# Peripherial.net
KiCad netlist of a schematic drawn in Altium Designer
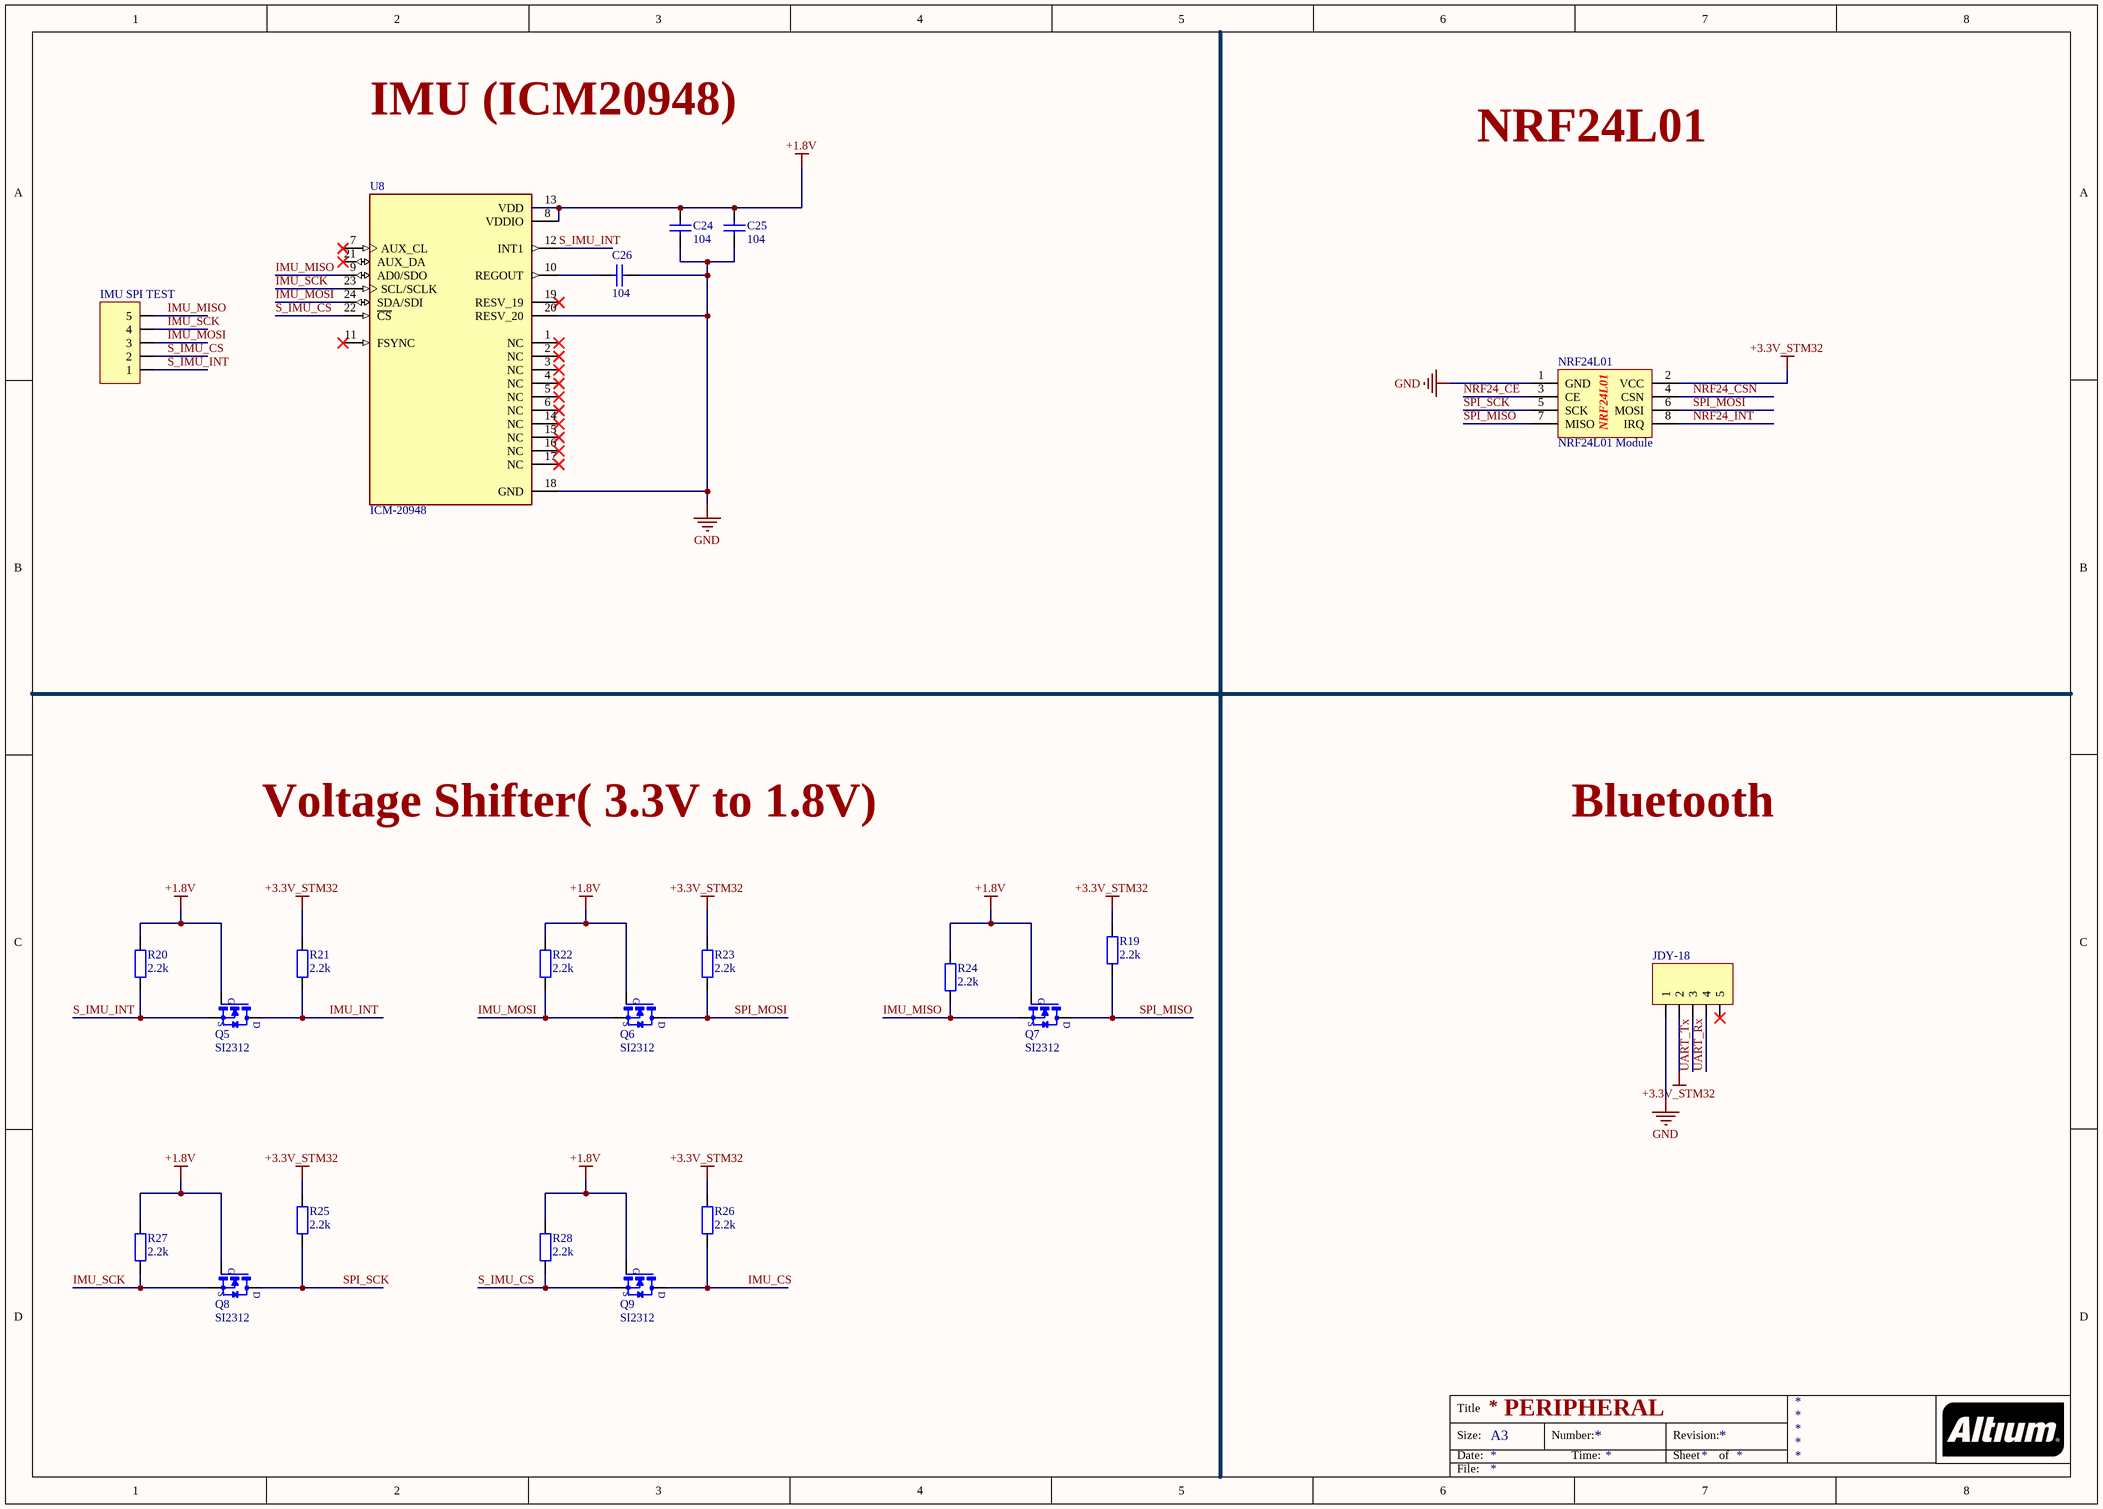
[diagram p0: Peripherial.SchDoc]

(export (version "E")
  (design (tool "Eeschema 10.0.6"))
  (components
    (comp (ref "C24")
      (value "104")
      (footprint "tu 1206")
      (description "Dán")
      (libsource (lib "Altium_Lib_by_KhueNguyenCreator") (part "Tu 1206 104 50V 20%"))
    )
    (comp (ref "C25")
      (value "104")
      (footprint "tu 1206")
      (description "Dán")
      (libsource (lib "Altium_Lib_by_KhueNguyenCreator") (part "Tu 1206 104 50V 20%"))
    )
    (comp (ref "C26")
      (value "104")
      (footprint "tu 1206")
      (description "Dán")
      (libsource (lib "Altium_Lib_by_KhueNguyenCreator") (part "Tu 1206 104 50V 20%"))
    )
    (comp (ref "IMU SPI TEST")
      (value "~")
      (footprint "JP 1x5 DT")
      (description "Cắm")
      (libsource (lib "Altium_Lib_by_KhueNguyenCreator") (part "JP 1x5 2.54 Duc Thang"))
    )
    (comp (ref "JDY-18")
      (value "JP 1x5 2.54")
      (footprint "JP 1x5 CC")
      (description "Cắm")
      (libsource (lib "Altium_Lib_by_KhueNguyenCreator") (part "JP 1x5 2.54 Cai Cong"))
    )
    (comp (ref "NRF24L01")
      (value "NRF24L01 Module")
      (footprint "NRF24L01")
      (libsource (lib "Altium_Lib_by_KhueNguyenCreator") (part "NRF24L01 Module"))
    )
    (comp (ref "Q5")
      (value "SI2312")
      (footprint "SI2312-TP:SOT23")
      (fields
        (field (name "MF") "{'manufacturer': u'Micro Commercial Components'}")
        (field (name "MP") "SI2312-TP")
      )
      (libsource (lib "*") (part "SI2312"))
    )
    (comp (ref "Q6")
      (value "SI2312")
      (footprint "SI2312-TP:SOT23")
      (fields
        (field (name "MF") "{'manufacturer': u'Micro Commercial Components'}")
        (field (name "MP") "SI2312-TP")
      )
      (libsource (lib "*") (part "SI2312"))
    )
    (comp (ref "Q7")
      (value "SI2312")
      (footprint "SI2312-TP:SOT23")
      (fields
        (field (name "MF") "{'manufacturer': u'Micro Commercial Components'}")
        (field (name "MP") "SI2312-TP")
      )
      (libsource (lib "*") (part "SI2312"))
    )
    (comp (ref "Q8")
      (value "SI2312")
      (footprint "SI2312-TP:SOT23")
      (fields
        (field (name "MF") "{'manufacturer': u'Micro Commercial Components'}")
        (field (name "MP") "SI2312-TP")
      )
      (libsource (lib "*") (part "SI2312"))
    )
    (comp (ref "Q9")
      (value "SI2312")
      (footprint "SI2312-TP:SOT23")
      (fields
        (field (name "MF") "{'manufacturer': u'Micro Commercial Components'}")
        (field (name "MP") "SI2312-TP")
      )
      (libsource (lib "*") (part "SI2312"))
    )
    (comp (ref "R19")
      (value "2.2k")
      (footprint "tro smd 0603")
      (description "Dán")
      (libsource (lib "Altium_Lib_by_KhueNguyenCreator") (part "Tro 0603 5% 2.2k"))
    )
    (comp (ref "R20")
      (value "2.2k")
      (footprint "tro smd 0603")
      (description "Dán")
      (libsource (lib "Altium_Lib_by_KhueNguyenCreator") (part "Tro 0603 5% 2.2k"))
    )
    (comp (ref "R21")
      (value "2.2k")
      (footprint "tro smd 0603")
      (description "Dán")
      (libsource (lib "Altium_Lib_by_KhueNguyenCreator") (part "Tro 0603 5% 2.2k"))
    )
    (comp (ref "R22")
      (value "2.2k")
      (footprint "tro smd 0603")
      (description "Dán")
      (libsource (lib "Altium_Lib_by_KhueNguyenCreator") (part "Tro 0603 5% 2.2k"))
    )
    (comp (ref "R23")
      (value "2.2k")
      (footprint "tro smd 0603")
      (description "Dán")
      (libsource (lib "Altium_Lib_by_KhueNguyenCreator") (part "Tro 0603 5% 2.2k"))
    )
    (comp (ref "R24")
      (value "2.2k")
      (footprint "tro smd 0603")
      (description "Dán")
      (libsource (lib "Altium_Lib_by_KhueNguyenCreator") (part "Tro 0603 5% 2.2k"))
    )
    (comp (ref "R25")
      (value "2.2k")
      (footprint "tro smd 0603")
      (description "Dán")
      (libsource (lib "Altium_Lib_by_KhueNguyenCreator") (part "Tro 0603 5% 2.2k"))
    )
    (comp (ref "R26")
      (value "2.2k")
      (footprint "tro smd 0603")
      (description "Dán")
      (libsource (lib "Altium_Lib_by_KhueNguyenCreator") (part "Tro 0603 5% 2.2k"))
    )
    (comp (ref "R27")
      (value "2.2k")
      (footprint "tro smd 0603")
      (description "Dán")
      (libsource (lib "Altium_Lib_by_KhueNguyenCreator") (part "Tro 0603 5% 2.2k"))
    )
    (comp (ref "R28")
      (value "2.2k")
      (footprint "tro smd 0603")
      (description "Dán")
      (libsource (lib "Altium_Lib_by_KhueNguyenCreator") (part "Tro 0603 5% 2.2k"))
    )
    (comp (ref "U8")
      (value "ICM-20948")
      (footprint "QFN40P300X300X105-24N")
      (description "Accelerometer, Gyroscope, Magnetometer, 9 Axis Sensor IÂ²C, SPI Output")
      (fields (field (name "MF") "{'manufacturer': u'TDK InvenSense'}"))
      (libsource (lib "SnapEDA_Library") (part "ICM-20948"))
    )
  )
  (nets
    (net (code "1") (name "+1.8V") (class "Default")
      (node (ref "C24") (pin "1") (pinfunction "1_1") (pintype "passive"))
      (node (ref "C25") (pin "1") (pinfunction "1_1") (pintype "passive"))
      (node (ref "Q5") (pin "1") (pinfunction "G_1") (pintype "passive"))
      (node (ref "Q6") (pin "1") (pinfunction "G_1") (pintype "passive"))
      (node (ref "Q7") (pin "1") (pinfunction "G_1") (pintype "passive"))
      (node (ref "Q8") (pin "1") (pinfunction "G_1") (pintype "passive"))
      (node (ref "Q9") (pin "1") (pinfunction "G_1") (pintype "passive"))
      (node (ref "R20") (pin "2") (pinfunction "2_2") (pintype "passive"))
      (node (ref "R22") (pin "2") (pinfunction "2_2") (pintype "passive"))
      (node (ref "R24") (pin "2") (pinfunction "2_2") (pintype "passive"))
      (node (ref "R27") (pin "2") (pinfunction "2_2") (pintype "passive"))
      (node (ref "R28") (pin "2") (pinfunction "2_2") (pintype "passive"))
      (node (ref "U8") (pin "13") (pinfunction "VDD_13") (pintype "power_in"))
      (node (ref "U8") (pin "8") (pinfunction "VDDIO_8") (pintype "power_in"))
    )
    (net (code "2") (name "+3.3V_STM32") (class "Default")
      (node (ref "JDY-18") (pin "2") (pinfunction "2_2") (pintype "passive"))
      (node (ref "NRF24L01") (pin "2") (pinfunction "VCC_2") (pintype "passive"))
      (node (ref "R19") (pin "2") (pinfunction "2_2") (pintype "passive"))
      (node (ref "R21") (pin "2") (pinfunction "2_2") (pintype "passive"))
      (node (ref "R23") (pin "2") (pinfunction "2_2") (pintype "passive"))
      (node (ref "R25") (pin "2") (pinfunction "2_2") (pintype "passive"))
      (node (ref "R26") (pin "2") (pinfunction "2_2") (pintype "passive"))
    )
    (net (code "3") (name "/IMU_CS") (class "Default")
      (node (ref "Q9") (pin "3") (pinfunction "D_3") (pintype "passive"))
      (node (ref "R26") (pin "1") (pinfunction "1_1") (pintype "passive"))
    )
    (net (code "4") (name "/IMU_INT") (class "Default")
      (node (ref "Q5") (pin "3") (pinfunction "D_3") (pintype "passive"))
      (node (ref "R21") (pin "1") (pinfunction "1_1") (pintype "passive"))
    )
    (net (code "5") (name "/IMU_MISO") (class "Default")
      (node (ref "IMU SPI TEST") (pin "5") (pinfunction "5_5") (pintype "passive"))
      (node (ref "Q7") (pin "2") (pinfunction "S_2") (pintype "passive"))
      (node (ref "R24") (pin "1") (pinfunction "1_1") (pintype "passive"))
      (node (ref "U8") (pin "9") (pinfunction "AD0/SDO_9") (pintype "bidirectional"))
    )
    (net (code "6") (name "/IMU_MOSI") (class "Default")
      (node (ref "IMU SPI TEST") (pin "3") (pinfunction "3_3") (pintype "passive"))
      (node (ref "Q6") (pin "2") (pinfunction "S_2") (pintype "passive"))
      (node (ref "R22") (pin "1") (pinfunction "1_1") (pintype "passive"))
      (node (ref "U8") (pin "24") (pinfunction "SDA/SDI_24") (pintype "bidirectional"))
    )
    (net (code "7") (name "/IMU_SCK") (class "Default")
      (node (ref "IMU SPI TEST") (pin "4") (pinfunction "4_4") (pintype "passive"))
      (node (ref "Q8") (pin "2") (pinfunction "S_2") (pintype "passive"))
      (node (ref "R27") (pin "1") (pinfunction "1_1") (pintype "passive"))
      (node (ref "U8") (pin "23") (pinfunction "SCL/SCLK_23") (pintype "input"))
    )
    (net (code "8") (name "/NRF24_CE") (class "Default")
      (node (ref "NRF24L01") (pin "3") (pinfunction "CE_3") (pintype "passive"))
    )
    (net (code "9") (name "/NRF24_CSN") (class "Default")
      (node (ref "NRF24L01") (pin "4") (pinfunction "CSN_4") (pintype "passive"))
    )
    (net (code "10") (name "/NRF24_INT") (class "Default")
      (node (ref "NRF24L01") (pin "8") (pinfunction "IRQ_8") (pintype "passive"))
    )
    (net (code "11") (name "/SPI_MISO") (class "Default")
      (node (ref "NRF24L01") (pin "7") (pinfunction "MISO_7") (pintype "passive"))
      (node (ref "Q7") (pin "3") (pinfunction "D_3") (pintype "passive"))
      (node (ref "R19") (pin "1") (pinfunction "1_1") (pintype "passive"))
    )
    (net (code "12") (name "/SPI_MOSI") (class "Default")
      (node (ref "NRF24L01") (pin "6") (pinfunction "MOSI_6") (pintype "passive"))
      (node (ref "Q6") (pin "3") (pinfunction "D_3") (pintype "passive"))
      (node (ref "R23") (pin "1") (pinfunction "1_1") (pintype "passive"))
    )
    (net (code "13") (name "/SPI_SCK") (class "Default")
      (node (ref "NRF24L01") (pin "5") (pinfunction "SCK_5") (pintype "passive"))
      (node (ref "Q8") (pin "3") (pinfunction "D_3") (pintype "passive"))
      (node (ref "R25") (pin "1") (pinfunction "1_1") (pintype "passive"))
    )
    (net (code "14") (name "/S_IMU_CS") (class "Default")
      (node (ref "IMU SPI TEST") (pin "2") (pinfunction "2_2") (pintype "passive"))
      (node (ref "Q9") (pin "2") (pinfunction "S_2") (pintype "passive"))
      (node (ref "R28") (pin "1") (pinfunction "1_1") (pintype "passive"))
      (node (ref "U8") (pin "22") (pinfunction "~{CS}_22") (pintype "input"))
    )
    (net (code "15") (name "/S_IMU_INT") (class "Default")
      (node (ref "IMU SPI TEST") (pin "1") (pinfunction "1_1") (pintype "passive"))
      (node (ref "Q5") (pin "2") (pinfunction "S_2") (pintype "passive"))
      (node (ref "R20") (pin "1") (pinfunction "1_1") (pintype "passive"))
      (node (ref "U8") (pin "12") (pinfunction "INT1_12") (pintype "output"))
    )
    (net (code "16") (name "/UART_Rx") (class "Default")
      (node (ref "JDY-18") (pin "4") (pinfunction "4_4") (pintype "passive"))
    )
    (net (code "17") (name "/UART_Tx") (class "Default")
      (node (ref "JDY-18") (pin "3") (pinfunction "3_3") (pintype "passive"))
    )
    (net (code "18") (name "GND") (class "Default")
      (node (ref "C24") (pin "2") (pinfunction "2_2") (pintype "passive"))
      (node (ref "C25") (pin "2") (pinfunction "2_2") (pintype "passive"))
      (node (ref "C26") (pin "2") (pinfunction "2_2") (pintype "passive"))
      (node (ref "JDY-18") (pin "1") (pinfunction "1_1") (pintype "passive"))
      (node (ref "NRF24L01") (pin "1") (pinfunction "GND_1") (pintype "passive"))
      (node (ref "U8") (pin "18") (pinfunction "GND_18") (pintype "power_in"))
      (node (ref "U8") (pin "20") (pinfunction "RESV_20_20") (pintype "passive"))
    )
    (net (code "19") (name "Net-(U8-REGOUT)") (class "Default")
      (node (ref "C26") (pin "1") (pinfunction "1_1") (pintype "passive"))
      (node (ref "U8") (pin "10") (pinfunction "REGOUT_10") (pintype "output"))
    )
    (net (code "20") (name "unconnected-(JDY-18-Pad5)") (class "Default")
      (node (ref "JDY-18") (pin "5") (pinfunction "5_5") (pintype "passive+no_connect"))
    )
    (net (code "21") (name "unconnected-(U8-AUX_CL-Pad7)") (class "Default")
      (node (ref "U8") (pin "7") (pinfunction "AUX_CL_7") (pintype "input+no_connect"))
    )
    (net (code "22") (name "unconnected-(U8-AUX_DA-Pad21)") (class "Default")
      (node (ref "U8") (pin "21") (pinfunction "AUX_DA_21") (pintype "bidirectional+no_connect"))
    )
    (net (code "23") (name "unconnected-(U8-FSYNC-Pad11)") (class "Default")
      (node (ref "U8") (pin "11") (pinfunction "FSYNC_11") (pintype "input+no_connect"))
    )
    (net (code "24") (name "unconnected-(U8-NC-Pad1)") (class "Default")
      (node (ref "U8") (pin "1") (pinfunction "NC_1") (pintype "passive+no_connect"))
    )
    (net (code "25") (name "unconnected-(U8-NC-Pad2)") (class "Default")
      (node (ref "U8") (pin "2") (pinfunction "NC_2") (pintype "passive+no_connect"))
    )
    (net (code "26") (name "unconnected-(U8-NC-Pad3)") (class "Default")
      (node (ref "U8") (pin "3") (pinfunction "NC_3") (pintype "passive+no_connect"))
    )
    (net (code "27") (name "unconnected-(U8-NC-Pad4)") (class "Default")
      (node (ref "U8") (pin "4") (pinfunction "NC_4") (pintype "passive+no_connect"))
    )
    (net (code "28") (name "unconnected-(U8-NC-Pad5)") (class "Default")
      (node (ref "U8") (pin "5") (pinfunction "NC_5") (pintype "passive+no_connect"))
    )
    (net (code "29") (name "unconnected-(U8-NC-Pad6)") (class "Default")
      (node (ref "U8") (pin "6") (pinfunction "NC_6") (pintype "passive+no_connect"))
    )
    (net (code "30") (name "unconnected-(U8-NC-Pad14)") (class "Default")
      (node (ref "U8") (pin "14") (pinfunction "NC_14") (pintype "passive+no_connect"))
    )
    (net (code "31") (name "unconnected-(U8-NC-Pad15)") (class "Default")
      (node (ref "U8") (pin "15") (pinfunction "NC_15") (pintype "passive+no_connect"))
    )
    (net (code "32") (name "unconnected-(U8-NC-Pad16)") (class "Default")
      (node (ref "U8") (pin "16") (pinfunction "NC_16") (pintype "passive+no_connect"))
    )
    (net (code "33") (name "unconnected-(U8-NC-Pad17)") (class "Default")
      (node (ref "U8") (pin "17") (pinfunction "NC_17") (pintype "passive+no_connect"))
    )
    (net (code "34") (name "unconnected-(U8-RESV_19-Pad19)") (class "Default")
      (node (ref "U8") (pin "19") (pinfunction "RESV_19_19") (pintype "passive+no_connect"))
    )
  )
)
